# Mainboard.net
KiCad netlist of a schematic drawn in EAGLE
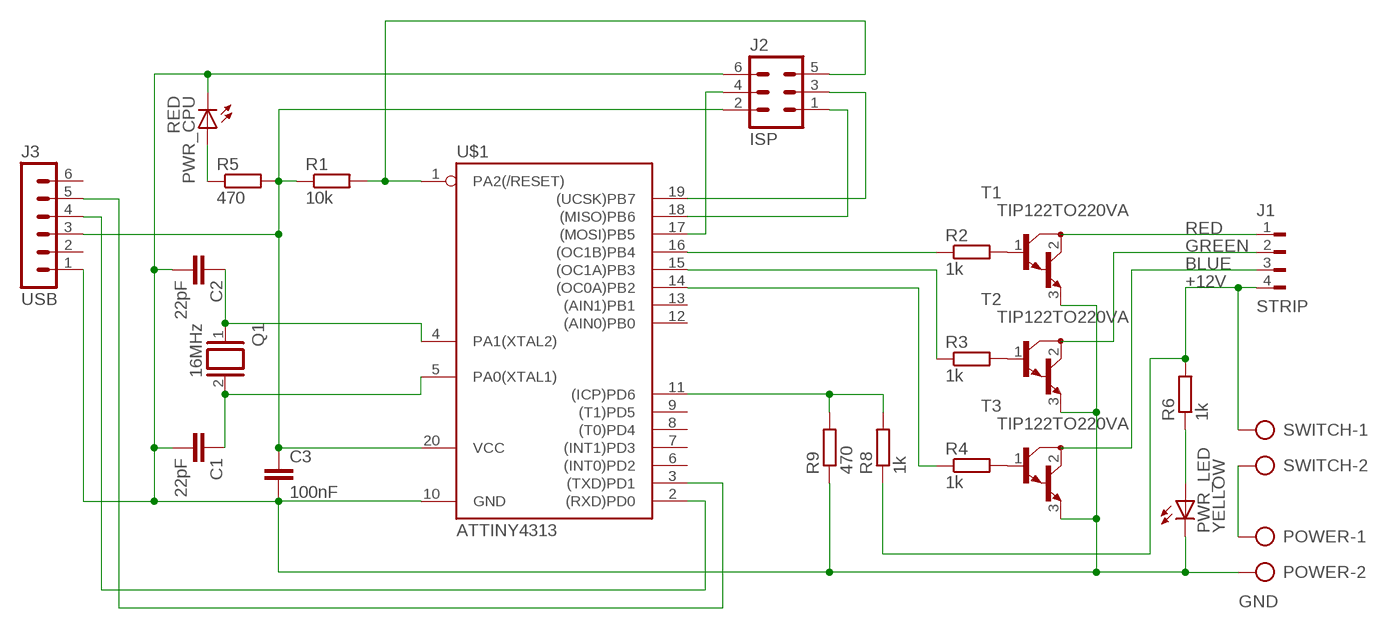
[diagram p0: schematic, sheet 1]

(export (version "E")
  (design (tool "Eeschema 10.0.6"))
  (components
    (comp (ref "C1")
      (value "22pF")
      (footprint "eagle-import:C025-024X044")
      (libsource (lib "eagle-import") (part "C-EU025-024X044"))
    )
    (comp (ref "C2")
      (value "22pF")
      (footprint "eagle-import:C025-024X044")
      (libsource (lib "eagle-import") (part "C-EU025-024X044"))
    )
    (comp (ref "C3")
      (value "100nF")
      (footprint "eagle-import:C025-024X044")
      (libsource (lib "eagle-import") (part "C-EU025-024X044"))
    )
    (comp (ref "J1")
      (value "STRIP")
      (footprint "eagle-import:FLOP-4V")
      (libsource (lib "eagle-import") (part "FLOP-4W"))
    )
    (comp (ref "J2")
      (value "ISP")
      (footprint "eagle-import:ML6")
      (libsource (lib "eagle-import") (part "ML6"))
    )
    (comp (ref "J3")
      (value "USB")
      (footprint "eagle-import:MA06-1")
      (libsource (lib "eagle-import") (part "MA06-1"))
    )
    (comp (ref "POWER")
      (value "AK500/2")
      (footprint "eagle-import:AK500_2")
      (libsource (lib "eagle-import") (part "AK500/2"))
    )
    (comp (ref "PWR_CPU")
      (value "RED")
      (footprint "eagle-import:LED2X5")
      (libsource (lib "eagle-import") (part "LEDSQR2X5"))
    )
    (comp (ref "PWR_LED")
      (value "YELLOW")
      (footprint "eagle-import:LED2X5")
      (libsource (lib "eagle-import") (part "LEDSQR2X5"))
    )
    (comp (ref "Q1")
      (value "16MHz")
      (footprint "eagle-import:QS")
      (libsource (lib "eagle-import") (part "XTAL/S"))
    )
    (comp (ref "R1")
      (value "10k")
      (footprint "eagle-import:0204_7")
      (libsource (lib "eagle-import") (part "R-EU_0204/7"))
    )
    (comp (ref "R2")
      (value "1k")
      (footprint "eagle-import:0204_7")
      (libsource (lib "eagle-import") (part "R-EU_0204/7"))
    )
    (comp (ref "R3")
      (value "1k")
      (footprint "eagle-import:0204_7")
      (libsource (lib "eagle-import") (part "R-EU_0204/7"))
    )
    (comp (ref "R4")
      (value "1k")
      (footprint "eagle-import:0204_7")
      (libsource (lib "eagle-import") (part "R-EU_0204/7"))
    )
    (comp (ref "R5")
      (value "470")
      (footprint "eagle-import:0204_7")
      (libsource (lib "eagle-import") (part "R-EU_0204/7"))
    )
    (comp (ref "R6")
      (value "1k")
      (footprint "eagle-import:0204_7")
      (libsource (lib "eagle-import") (part "R-EU_0204/7"))
    )
    (comp (ref "R8")
      (value "1k")
      (footprint "eagle-import:0204_7")
      (libsource (lib "eagle-import") (part "R-EU_0204/7"))
    )
    (comp (ref "R9")
      (value "470")
      (footprint "eagle-import:0204_7")
      (libsource (lib "eagle-import") (part "R-EU_0204/7"))
    )
    (comp (ref "SWITCH")
      (value "AK500/2")
      (footprint "eagle-import:AK500_2")
      (libsource (lib "eagle-import") (part "AK500/2"))
    )
    (comp (ref "T1")
      (value "TIP122TO220VA")
      (footprint "eagle-import:TO220AV")
      (libsource (lib "eagle-import") (part "TIP122TO220VA"))
    )
    (comp (ref "T2")
      (value "TIP122TO220VA")
      (footprint "eagle-import:TO220AV")
      (libsource (lib "eagle-import") (part "TIP122TO220VA"))
    )
    (comp (ref "T3")
      (value "TIP122TO220VA")
      (footprint "eagle-import:TO220AV")
      (libsource (lib "eagle-import") (part "TIP122TO220VA"))
    )
    (comp (ref "U$1")
      (value "ATTINY4313")
      (footprint "eagle-import:DIL20")
      (libsource (lib "eagle-import") (part "TINY2313-P"))
    )
  )
  (nets
    (net (code "1") (name "/+12V") (class "Default")
      (node (ref "J1") (pin "4") (pinfunction "4_4") (pintype "passive"))
      (node (ref "R6") (pin "2") (pinfunction "2_2") (pintype "passive"))
      (node (ref "R8") (pin "1") (pinfunction "1_1") (pintype "passive"))
      (node (ref "SWITCH") (pin "1") (pinfunction "KL_1") (pintype "passive"))
    )
    (net (code "2") (name "/BLUE") (class "Default")
      (node (ref "J1") (pin "3") (pinfunction "3_3") (pintype "passive"))
      (node (ref "T3") (pin "2") (pinfunction "C_2") (pintype "passive"))
    )
    (net (code "3") (name "/GND") (class "Default")
      (node (ref "C1") (pin "2") (pinfunction "2_2") (pintype "passive"))
      (node (ref "C2") (pin "2") (pinfunction "2_2") (pintype "passive"))
      (node (ref "C3") (pin "2") (pinfunction "2_2") (pintype "passive"))
      (node (ref "J2") (pin "6") (pinfunction "6_6") (pintype "passive"))
      (node (ref "J3") (pin "1") (pinfunction "1_1") (pintype "passive"))
      (node (ref "POWER") (pin "2") (pinfunction "KL_2") (pintype "passive"))
      (node (ref "PWR_CPU") (pin "K") (pinfunction "C_K") (pintype "passive"))
      (node (ref "PWR_LED") (pin "K") (pinfunction "C_K") (pintype "passive"))
      (node (ref "R9") (pin "1") (pinfunction "1_1") (pintype "passive"))
      (node (ref "T1") (pin "3") (pinfunction "E_3") (pintype "passive"))
      (node (ref "T2") (pin "3") (pinfunction "E_3") (pintype "passive"))
      (node (ref "T3") (pin "3") (pinfunction "E_3") (pintype "passive"))
      (node (ref "U$1") (pin "10") (pinfunction "GND_10") (pintype "power_in"))
    )
    (net (code "4") (name "/GREEN") (class "Default")
      (node (ref "J1") (pin "2") (pinfunction "2_2") (pintype "passive"))
      (node (ref "T2") (pin "2") (pinfunction "C_2") (pintype "passive"))
    )
    (net (code "5") (name "/RED") (class "Default")
      (node (ref "J1") (pin "1") (pinfunction "1_1") (pintype "passive"))
      (node (ref "T1") (pin "2") (pinfunction "C_2") (pintype "passive"))
    )
    (net (code "6") (name "Net-(POWERA-KL)") (class "Default")
      (node (ref "POWER") (pin "1") (pinfunction "KL_1") (pintype "passive"))
      (node (ref "SWITCH") (pin "2") (pinfunction "KL_2") (pintype "passive"))
    )
    (net (code "7") (name "Net-(PWR_CPU-PadA)") (class "Default")
      (node (ref "PWR_CPU") (pin "A") (pinfunction "A_A") (pintype "passive"))
      (node (ref "R5") (pin "1") (pinfunction "1_1") (pintype "passive"))
    )
    (net (code "8") (name "Net-(PWR_LED-PadA)") (class "Default")
      (node (ref "PWR_LED") (pin "A") (pinfunction "A_A") (pintype "passive"))
      (node (ref "R6") (pin "1") (pinfunction "1_1") (pintype "passive"))
    )
    (net (code "9") (name "Net-(T1-B)") (class "Default")
      (node (ref "R2") (pin "2") (pinfunction "2_2") (pintype "passive"))
      (node (ref "T1") (pin "1") (pinfunction "B_1") (pintype "passive"))
    )
    (net (code "10") (name "Net-(T2-B)") (class "Default")
      (node (ref "R3") (pin "2") (pinfunction "2_2") (pintype "passive"))
      (node (ref "T2") (pin "1") (pinfunction "B_1") (pintype "passive"))
    )
    (net (code "11") (name "Net-(T3-B)") (class "Default")
      (node (ref "R4") (pin "2") (pinfunction "2_2") (pintype "passive"))
      (node (ref "T3") (pin "1") (pinfunction "B_1") (pintype "passive"))
    )
    (net (code "12") (name "Net-(U$1-(ICP)PD6)") (class "Default")
      (node (ref "R8") (pin "2") (pinfunction "2_2") (pintype "passive"))
      (node (ref "R9") (pin "2") (pinfunction "2_2") (pintype "passive"))
      (node (ref "U$1") (pin "11") (pinfunction "(ICP)PD6_11") (pintype "bidirectional"))
    )
    (net (code "13") (name "Net-(U$1-(MISO)PB6)") (class "Default")
      (node (ref "J2") (pin "1") (pinfunction "1_1") (pintype "passive"))
      (node (ref "U$1") (pin "18") (pinfunction "(MISO)PB6_18") (pintype "bidirectional"))
    )
    (net (code "14") (name "Net-(U$1-(MOSI)PB5)") (class "Default")
      (node (ref "J2") (pin "4") (pinfunction "4_4") (pintype "passive"))
      (node (ref "U$1") (pin "17") (pinfunction "(MOSI)PB5_17") (pintype "bidirectional"))
    )
    (net (code "15") (name "Net-(U$1-(OC0A)PB2)") (class "Default")
      (node (ref "R4") (pin "1") (pinfunction "1_1") (pintype "passive"))
      (node (ref "U$1") (pin "14") (pinfunction "(OC0A)PB2_14") (pintype "bidirectional"))
    )
    (net (code "16") (name "Net-(U$1-(OC1A)PB3)") (class "Default")
      (node (ref "R3") (pin "1") (pinfunction "1_1") (pintype "passive"))
      (node (ref "U$1") (pin "15") (pinfunction "(OC1A)PB3_15") (pintype "bidirectional"))
    )
    (net (code "17") (name "Net-(U$1-(OC1B)PB4)") (class "Default")
      (node (ref "R2") (pin "1") (pinfunction "1_1") (pintype "passive"))
      (node (ref "U$1") (pin "16") (pinfunction "(OC1B)PB4_16") (pintype "bidirectional"))
    )
    (net (code "18") (name "Net-(U$1-(RXD)PD0)") (class "Default")
      (node (ref "J3") (pin "4") (pinfunction "4_4") (pintype "passive"))
      (node (ref "U$1") (pin "2") (pinfunction "(RXD)PD0_2") (pintype "bidirectional"))
    )
    (net (code "19") (name "Net-(U$1-(TXD)PD1)") (class "Default")
      (node (ref "J3") (pin "5") (pinfunction "5_5") (pintype "passive"))
      (node (ref "U$1") (pin "3") (pinfunction "(TXD)PD1_3") (pintype "bidirectional"))
    )
    (net (code "20") (name "Net-(U$1-(UCSK)PB7)") (class "Default")
      (node (ref "J2") (pin "3") (pinfunction "3_3") (pintype "passive"))
      (node (ref "U$1") (pin "19") (pinfunction "(UCSK)PB7_19") (pintype "bidirectional"))
    )
    (net (code "21") (name "Net-(U$1-PA0(XTAL1))") (class "Default")
      (node (ref "C1") (pin "1") (pinfunction "1_1") (pintype "passive"))
      (node (ref "Q1") (pin "2") (pinfunction "2_2") (pintype "passive"))
      (node (ref "U$1") (pin "5") (pinfunction "PA0(XTAL1)_5") (pintype "bidirectional"))
    )
    (net (code "22") (name "Net-(U$1-PA1(XTAL2))") (class "Default")
      (node (ref "C2") (pin "1") (pinfunction "1_1") (pintype "passive"))
      (node (ref "Q1") (pin "1") (pinfunction "1_1") (pintype "passive"))
      (node (ref "U$1") (pin "4") (pinfunction "PA1(XTAL2)_4") (pintype "bidirectional"))
    )
    (net (code "23") (name "Net-(U$1-PA2({slash}RESET))") (class "Default")
      (node (ref "J2") (pin "5") (pinfunction "5_5") (pintype "passive"))
      (node (ref "R1") (pin "2") (pinfunction "2_2") (pintype "passive"))
      (node (ref "U$1") (pin "1") (pinfunction "PA2(/RESET)_1") (pintype "input"))
    )
    (net (code "24") (name "Net-(U$1-VCC)") (class "Default")
      (node (ref "C3") (pin "1") (pinfunction "1_1") (pintype "passive"))
      (node (ref "J2") (pin "2") (pinfunction "2_2") (pintype "passive"))
      (node (ref "J3") (pin "3") (pinfunction "3_3") (pintype "passive"))
      (node (ref "R1") (pin "1") (pinfunction "1_1") (pintype "passive"))
      (node (ref "R5") (pin "2") (pinfunction "2_2") (pintype "passive"))
      (node (ref "U$1") (pin "20") (pinfunction "VCC_20") (pintype "power_in"))
    )
    (net (code "25") (name "unconnected-(J3-Pad2)") (class "Default")
      (node (ref "J3") (pin "2") (pinfunction "2_2") (pintype "passive"))
    )
    (net (code "26") (name "unconnected-(J3-Pad6)") (class "Default")
      (node (ref "J3") (pin "6") (pinfunction "6_6") (pintype "passive"))
    )
    (net (code "27") (name "unconnected-(U$1-(AIN0)PB0-Pad12)") (class "Default")
      (node (ref "U$1") (pin "12") (pinfunction "(AIN0)PB0_12") (pintype "bidirectional"))
    )
    (net (code "28") (name "unconnected-(U$1-(AIN1)PB1-Pad13)") (class "Default")
      (node (ref "U$1") (pin "13") (pinfunction "(AIN1)PB1_13") (pintype "bidirectional"))
    )
    (net (code "29") (name "unconnected-(U$1-(INT0)PD2-Pad6)") (class "Default")
      (node (ref "U$1") (pin "6") (pinfunction "(INT0)PD2_6") (pintype "bidirectional"))
    )
    (net (code "30") (name "unconnected-(U$1-(INT1)PD3-Pad7)") (class "Default")
      (node (ref "U$1") (pin "7") (pinfunction "(INT1)PD3_7") (pintype "bidirectional"))
    )
    (net (code "31") (name "unconnected-(U$1-(T0)PD4-Pad8)") (class "Default")
      (node (ref "U$1") (pin "8") (pinfunction "(T0)PD4_8") (pintype "bidirectional"))
    )
    (net (code "32") (name "unconnected-(U$1-(T1)PD5-Pad9)") (class "Default")
      (node (ref "U$1") (pin "9") (pinfunction "(T1)PD5_9") (pintype "bidirectional"))
    )
  )
)
